# 4_Light_Screen.net
KiCad netlist of a schematic drawn in Altium Designer
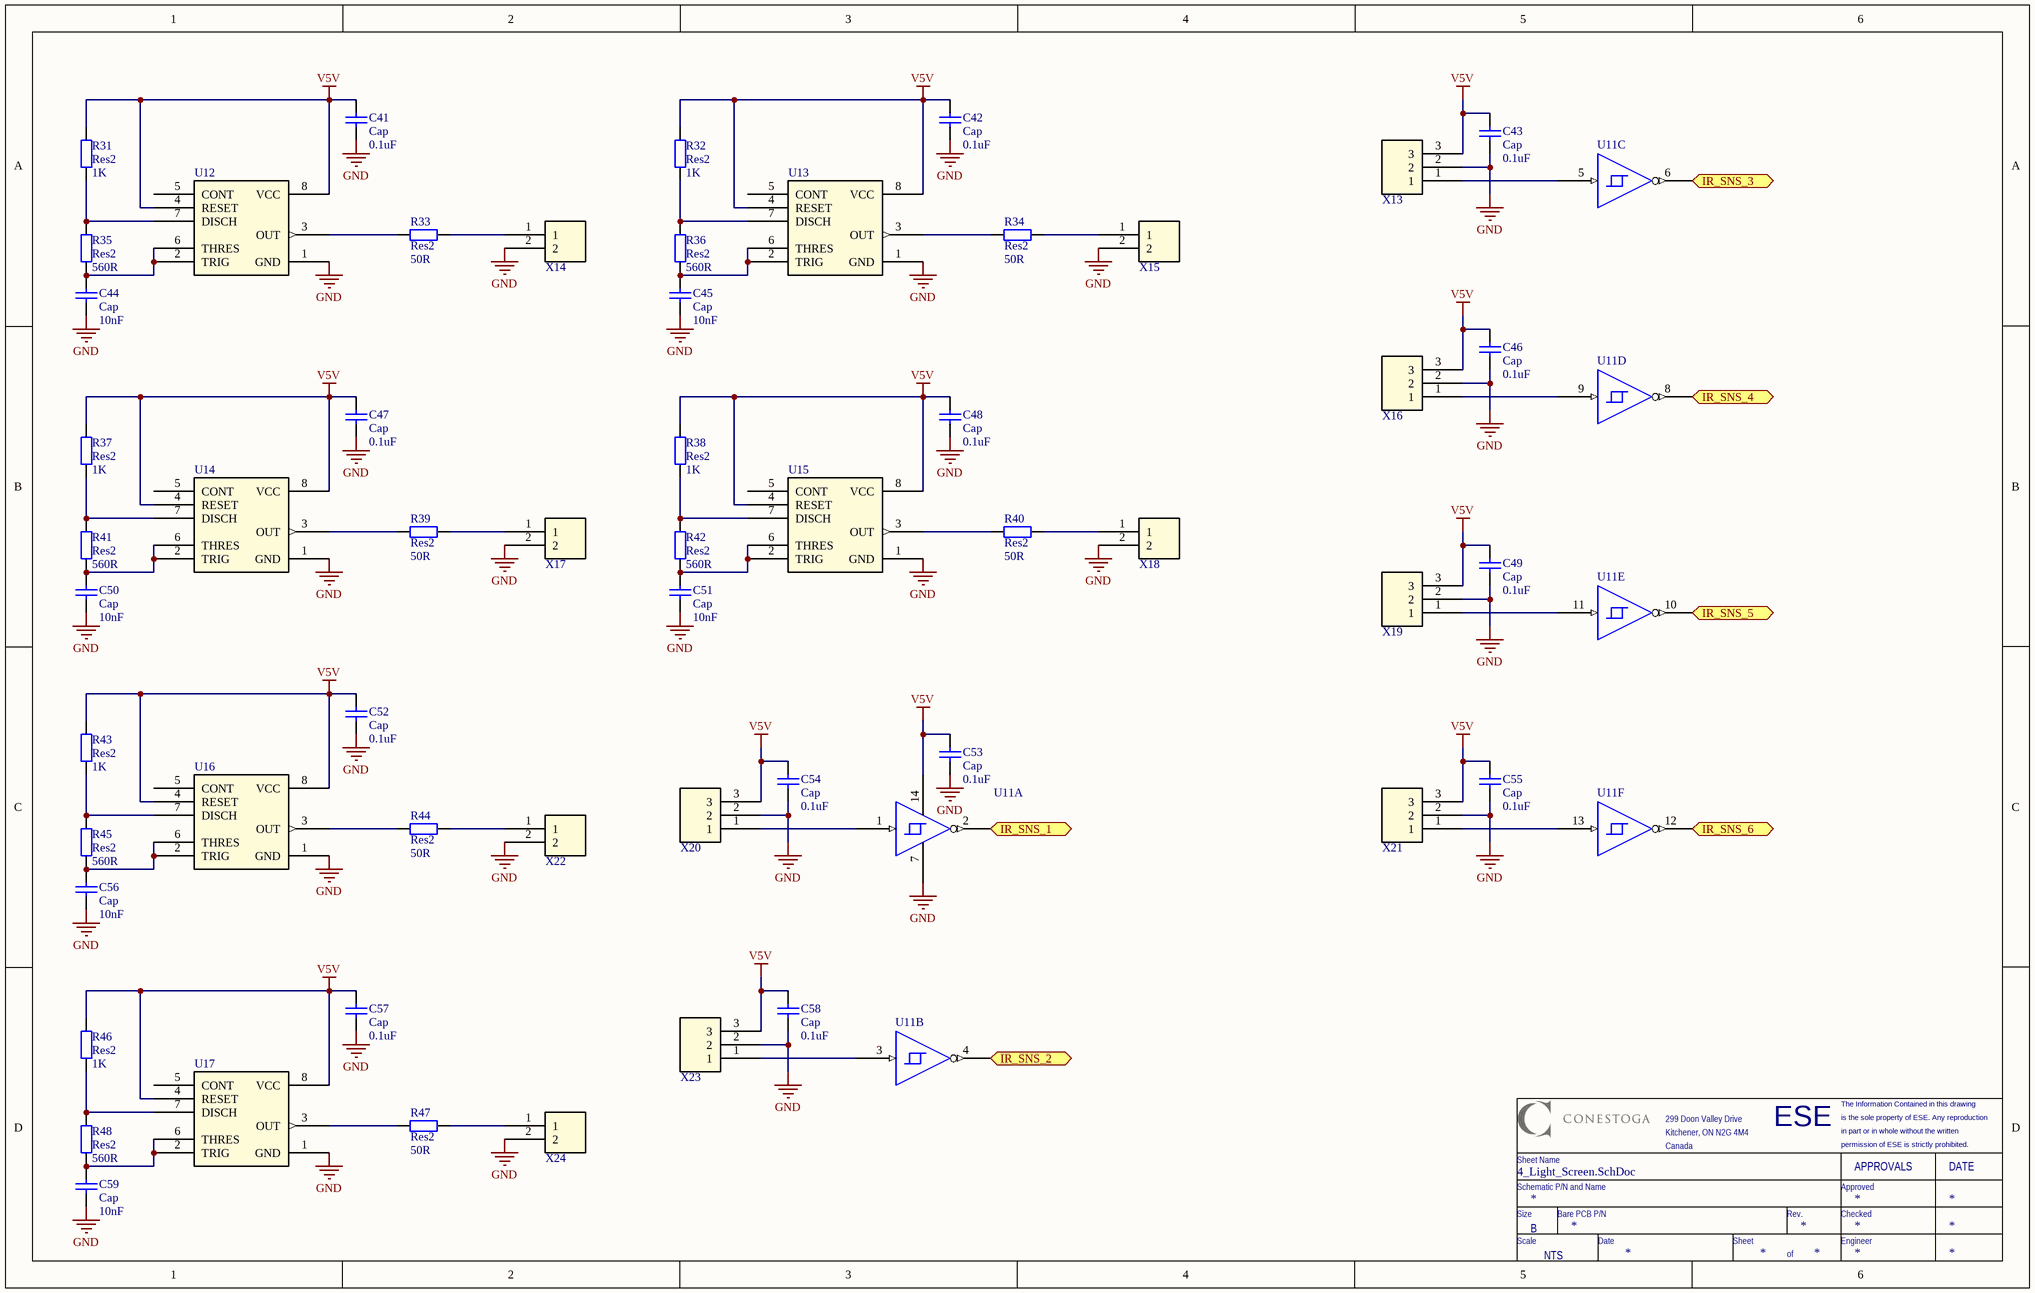
[diagram p0: 4_Light_Screen.SchDoc]

(export (version "E")
  (design (tool "Eeschema 10.0.6"))
  (components
    (comp (ref "C41")
      (value "Cap")
      (footprint "RAD-0.3")
      (description "Capacitor")
      (fields (field (name "ALTIUM_VALUE") "0.1uF") (field (name "PUBLISHER") "Altium Limited"))
      (libsource (lib "Miscellaneous Devices") (part "Cap"))
    )
    (comp (ref "C42")
      (value "Cap")
      (footprint "RAD-0.3")
      (description "Capacitor")
      (fields (field (name "ALTIUM_VALUE") "0.1uF") (field (name "PUBLISHER") "Altium Limited"))
      (libsource (lib "Miscellaneous Devices") (part "Cap"))
    )
    (comp (ref "C43")
      (value "Cap")
      (footprint "RAD-0.3")
      (description "Capacitor")
      (fields (field (name "ALTIUM_VALUE") "0.1uF") (field (name "PUBLISHER") "Altium Limited"))
      (libsource (lib "Miscellaneous Devices") (part "Cap"))
    )
    (comp (ref "C44")
      (value "Cap")
      (footprint "RAD-0.3")
      (description "Capacitor")
      (fields (field (name "ALTIUM_VALUE") "10nF") (field (name "PUBLISHER") "Altium Limited"))
      (libsource (lib "Miscellaneous Devices") (part "Cap"))
    )
    (comp (ref "C45")
      (value "Cap")
      (footprint "RAD-0.3")
      (description "Capacitor")
      (fields (field (name "ALTIUM_VALUE") "10nF") (field (name "PUBLISHER") "Altium Limited"))
      (libsource (lib "Miscellaneous Devices") (part "Cap"))
    )
    (comp (ref "C46")
      (value "Cap")
      (footprint "RAD-0.3")
      (description "Capacitor")
      (fields (field (name "ALTIUM_VALUE") "0.1uF") (field (name "PUBLISHER") "Altium Limited"))
      (libsource (lib "Miscellaneous Devices") (part "Cap"))
    )
    (comp (ref "C47")
      (value "Cap")
      (footprint "RAD-0.3")
      (description "Capacitor")
      (fields (field (name "ALTIUM_VALUE") "0.1uF") (field (name "PUBLISHER") "Altium Limited"))
      (libsource (lib "Miscellaneous Devices") (part "Cap"))
    )
    (comp (ref "C48")
      (value "Cap")
      (footprint "RAD-0.3")
      (description "Capacitor")
      (fields (field (name "ALTIUM_VALUE") "0.1uF") (field (name "PUBLISHER") "Altium Limited"))
      (libsource (lib "Miscellaneous Devices") (part "Cap"))
    )
    (comp (ref "C49")
      (value "Cap")
      (footprint "RAD-0.3")
      (description "Capacitor")
      (fields (field (name "ALTIUM_VALUE") "0.1uF") (field (name "PUBLISHER") "Altium Limited"))
      (libsource (lib "Miscellaneous Devices") (part "Cap"))
    )
    (comp (ref "C50")
      (value "Cap")
      (footprint "RAD-0.3")
      (description "Capacitor")
      (fields (field (name "ALTIUM_VALUE") "10nF") (field (name "PUBLISHER") "Altium Limited"))
      (libsource (lib "Miscellaneous Devices") (part "Cap"))
    )
    (comp (ref "C51")
      (value "Cap")
      (footprint "RAD-0.3")
      (description "Capacitor")
      (fields (field (name "ALTIUM_VALUE") "10nF") (field (name "PUBLISHER") "Altium Limited"))
      (libsource (lib "Miscellaneous Devices") (part "Cap"))
    )
    (comp (ref "C52")
      (value "Cap")
      (footprint "RAD-0.3")
      (description "Capacitor")
      (fields (field (name "ALTIUM_VALUE") "0.1uF") (field (name "PUBLISHER") "Altium Limited"))
      (libsource (lib "Miscellaneous Devices") (part "Cap"))
    )
    (comp (ref "C53")
      (value "Cap")
      (footprint "RAD-0.3")
      (description "Capacitor")
      (fields (field (name "ALTIUM_VALUE") "0.1uF") (field (name "PUBLISHER") "Altium Limited"))
      (libsource (lib "Miscellaneous Devices") (part "Cap"))
    )
    (comp (ref "C54")
      (value "Cap")
      (footprint "RAD-0.3")
      (description "Capacitor")
      (fields (field (name "ALTIUM_VALUE") "0.1uF") (field (name "PUBLISHER") "Altium Limited"))
      (libsource (lib "Miscellaneous Devices") (part "Cap"))
    )
    (comp (ref "C55")
      (value "Cap")
      (footprint "RAD-0.3")
      (description "Capacitor")
      (fields (field (name "ALTIUM_VALUE") "0.1uF") (field (name "PUBLISHER") "Altium Limited"))
      (libsource (lib "Miscellaneous Devices") (part "Cap"))
    )
    (comp (ref "C56")
      (value "Cap")
      (footprint "RAD-0.3")
      (description "Capacitor")
      (fields (field (name "ALTIUM_VALUE") "10nF") (field (name "PUBLISHER") "Altium Limited"))
      (libsource (lib "Miscellaneous Devices") (part "Cap"))
    )
    (comp (ref "C57")
      (value "Cap")
      (footprint "RAD-0.3")
      (description "Capacitor")
      (fields (field (name "ALTIUM_VALUE") "0.1uF") (field (name "PUBLISHER") "Altium Limited"))
      (libsource (lib "Miscellaneous Devices") (part "Cap"))
    )
    (comp (ref "C58")
      (value "Cap")
      (footprint "RAD-0.3")
      (description "Capacitor")
      (fields (field (name "ALTIUM_VALUE") "0.1uF") (field (name "PUBLISHER") "Altium Limited"))
      (libsource (lib "Miscellaneous Devices") (part "Cap"))
    )
    (comp (ref "C59")
      (value "Cap")
      (footprint "RAD-0.3")
      (description "Capacitor")
      (fields (field (name "ALTIUM_VALUE") "10nF") (field (name "PUBLISHER") "Altium Limited"))
      (libsource (lib "Miscellaneous Devices") (part "Cap"))
    )
    (comp (ref "R31")
      (value "Res2")
      (footprint "AXIAL-0.4")
      (description "Resistor")
      (fields (field (name "ALTIUM_VALUE") "1K") (field (name "PUBLISHER") "Altium Limited"))
      (libsource (lib "Miscellaneous Devices") (part "Res2"))
    )
    (comp (ref "R32")
      (value "Res2")
      (footprint "AXIAL-0.4")
      (description "Resistor")
      (fields (field (name "ALTIUM_VALUE") "1K") (field (name "PUBLISHER") "Altium Limited"))
      (libsource (lib "Miscellaneous Devices") (part "Res2"))
    )
    (comp (ref "R33")
      (value "Res2")
      (footprint "AXIAL-0.4")
      (description "Resistor")
      (fields (field (name "ALTIUM_VALUE") "50R") (field (name "PUBLISHER") "Altium Limited"))
      (libsource (lib "") (part "Res2_1"))
    )
    (comp (ref "R34")
      (value "Res2")
      (footprint "AXIAL-0.4")
      (description "Resistor")
      (fields (field (name "ALTIUM_VALUE") "50R") (field (name "PUBLISHER") "Altium Limited"))
      (libsource (lib "") (part "Res2_1"))
    )
    (comp (ref "R35")
      (value "Res2")
      (footprint "AXIAL-0.4")
      (description "Resistor")
      (fields (field (name "ALTIUM_VALUE") "560R") (field (name "PUBLISHER") "Altium Limited"))
      (libsource (lib "Miscellaneous Devices") (part "Res2"))
    )
    (comp (ref "R36")
      (value "Res2")
      (footprint "AXIAL-0.4")
      (description "Resistor")
      (fields (field (name "ALTIUM_VALUE") "560R") (field (name "PUBLISHER") "Altium Limited"))
      (libsource (lib "Miscellaneous Devices") (part "Res2"))
    )
    (comp (ref "R37")
      (value "Res2")
      (footprint "AXIAL-0.4")
      (description "Resistor")
      (fields (field (name "ALTIUM_VALUE") "1K") (field (name "PUBLISHER") "Altium Limited"))
      (libsource (lib "Miscellaneous Devices") (part "Res2"))
    )
    (comp (ref "R38")
      (value "Res2")
      (footprint "AXIAL-0.4")
      (description "Resistor")
      (fields (field (name "ALTIUM_VALUE") "1K") (field (name "PUBLISHER") "Altium Limited"))
      (libsource (lib "Miscellaneous Devices") (part "Res2"))
    )
    (comp (ref "R39")
      (value "Res2")
      (footprint "AXIAL-0.4")
      (description "Resistor")
      (fields (field (name "ALTIUM_VALUE") "50R") (field (name "PUBLISHER") "Altium Limited"))
      (libsource (lib "") (part "Res2_1"))
    )
    (comp (ref "R40")
      (value "Res2")
      (footprint "AXIAL-0.4")
      (description "Resistor")
      (fields (field (name "ALTIUM_VALUE") "50R") (field (name "PUBLISHER") "Altium Limited"))
      (libsource (lib "") (part "Res2_1"))
    )
    (comp (ref "R41")
      (value "Res2")
      (footprint "AXIAL-0.4")
      (description "Resistor")
      (fields (field (name "ALTIUM_VALUE") "560R") (field (name "PUBLISHER") "Altium Limited"))
      (libsource (lib "Miscellaneous Devices") (part "Res2"))
    )
    (comp (ref "R42")
      (value "Res2")
      (footprint "AXIAL-0.4")
      (description "Resistor")
      (fields (field (name "ALTIUM_VALUE") "560R") (field (name "PUBLISHER") "Altium Limited"))
      (libsource (lib "Miscellaneous Devices") (part "Res2"))
    )
    (comp (ref "R43")
      (value "Res2")
      (footprint "AXIAL-0.4")
      (description "Resistor")
      (fields (field (name "ALTIUM_VALUE") "1K") (field (name "PUBLISHER") "Altium Limited"))
      (libsource (lib "Miscellaneous Devices") (part "Res2"))
    )
    (comp (ref "R44")
      (value "Res2")
      (footprint "AXIAL-0.4")
      (description "Resistor")
      (fields (field (name "ALTIUM_VALUE") "50R") (field (name "PUBLISHER") "Altium Limited"))
      (libsource (lib "") (part "Res2_1"))
    )
    (comp (ref "R45")
      (value "Res2")
      (footprint "AXIAL-0.4")
      (description "Resistor")
      (fields (field (name "ALTIUM_VALUE") "560R") (field (name "PUBLISHER") "Altium Limited"))
      (libsource (lib "Miscellaneous Devices") (part "Res2"))
    )
    (comp (ref "R46")
      (value "Res2")
      (footprint "AXIAL-0.4")
      (description "Resistor")
      (fields (field (name "ALTIUM_VALUE") "1K") (field (name "PUBLISHER") "Altium Limited"))
      (libsource (lib "Miscellaneous Devices") (part "Res2"))
    )
    (comp (ref "R47")
      (value "Res2")
      (footprint "AXIAL-0.4")
      (description "Resistor")
      (fields (field (name "ALTIUM_VALUE") "50R") (field (name "PUBLISHER") "Altium Limited"))
      (libsource (lib "") (part "Res2_1"))
    )
    (comp (ref "R48")
      (value "Res2")
      (footprint "AXIAL-0.4")
      (description "Resistor")
      (fields (field (name "ALTIUM_VALUE") "560R") (field (name "PUBLISHER") "Altium Limited"))
      (libsource (lib "Miscellaneous Devices") (part "Res2"))
    )
    (comp (ref "U11")
      (value "IC HEX SCHMITT-TRIG INV 14-DIP")
      (footprint "14-DIP")
      (fields
        (field (name "DIGI-KEY_PART_NUMBER") "296-4368-5-ND")
        (field (name "MANUFACTUER_PART_NUMBER") "SN74ACT14N")
        (field (name "MANUFACTURER") "Texas Instruments")
      )
      (libsource (lib "thomas_lib") (part "IC HEX SCHMITT-TRIG INV 14-DIP"))
    )
    (comp (ref "U12")
      (value "IC OSC SINGLE TIMER 100KHZ 8-DIP")
      (footprint "thomas_lib:8-DIP")
      (fields
        (field (name "MANUFACTURER_PART_NUMBER") "NE555P")
        (field (name "DIGI-KEY_PART_NUMBER") "296-1411-5-ND")
        (field (name "MANUFACTURER") "Texas Instruments")
      )
      (libsource (lib "thomas_lib") (part "IC OSC SINGLE TIMER 100KHZ 8-DIP"))
    )
    (comp (ref "U13")
      (value "IC OSC SINGLE TIMER 100KHZ 8-DIP")
      (footprint "thomas_lib:8-DIP")
      (fields
        (field (name "MANUFACTURER_PART_NUMBER") "NE555P")
        (field (name "DIGI-KEY_PART_NUMBER") "296-1411-5-ND")
        (field (name "MANUFACTURER") "Texas Instruments")
      )
      (libsource (lib "thomas_lib") (part "IC OSC SINGLE TIMER 100KHZ 8-DIP"))
    )
    (comp (ref "U14")
      (value "IC OSC SINGLE TIMER 100KHZ 8-DIP")
      (footprint "thomas_lib:8-DIP")
      (fields
        (field (name "MANUFACTURER_PART_NUMBER") "NE555P")
        (field (name "DIGI-KEY_PART_NUMBER") "296-1411-5-ND")
        (field (name "MANUFACTURER") "Texas Instruments")
      )
      (libsource (lib "thomas_lib") (part "IC OSC SINGLE TIMER 100KHZ 8-DIP"))
    )
    (comp (ref "U15")
      (value "IC OSC SINGLE TIMER 100KHZ 8-DIP")
      (footprint "thomas_lib:8-DIP")
      (fields
        (field (name "MANUFACTURER_PART_NUMBER") "NE555P")
        (field (name "DIGI-KEY_PART_NUMBER") "296-1411-5-ND")
        (field (name "MANUFACTURER") "Texas Instruments")
      )
      (libsource (lib "thomas_lib") (part "IC OSC SINGLE TIMER 100KHZ 8-DIP"))
    )
    (comp (ref "U16")
      (value "IC OSC SINGLE TIMER 100KHZ 8-DIP")
      (footprint "thomas_lib:8-DIP")
      (fields
        (field (name "MANUFACTURER_PART_NUMBER") "NE555P")
        (field (name "DIGI-KEY_PART_NUMBER") "296-1411-5-ND")
        (field (name "MANUFACTURER") "Texas Instruments")
      )
      (libsource (lib "thomas_lib") (part "IC OSC SINGLE TIMER 100KHZ 8-DIP"))
    )
    (comp (ref "U17")
      (value "IC OSC SINGLE TIMER 100KHZ 8-DIP")
      (footprint "thomas_lib:8-DIP")
      (fields
        (field (name "MANUFACTURER_PART_NUMBER") "NE555P")
        (field (name "DIGI-KEY_PART_NUMBER") "296-1411-5-ND")
        (field (name "MANUFACTURER") "Texas Instruments")
      )
      (libsource (lib "thomas_lib") (part "IC OSC SINGLE TIMER 100KHZ 8-DIP"))
    )
    (comp (ref "X13")
      (value "TERM BLOCK HDR 3POS VERT 3.5MM")
      (footprint "WR-TBL-3211 3")
      (fields
        (field (name "DIGIKEY_PART_NUMBER") "732-2764-ND")
        (field (name "MANUFACTURER_PART_NUMBER") "691321100003")
        (field (name "MANUFACTURER") "Wurth Electronics Inc")
      )
      (libsource (lib "thomas_lib") (part "TERM BLOCK HDR 3POS VERT 3.5MM"))
    )
    (comp (ref "X14")
      (value "TERM BLOCK HDR 2POS VERT 3.5MM")
      (footprint "WR-TBL-3211 2")
      (fields
        (field (name "DIGIKEY_PART_NUMBER") "732-2763-ND")
        (field (name "MANUFACTURER_PART_NUMBER") "691321100002")
        (field (name "MANUFACTURER") "Wurth Electronics Inc")
      )
      (libsource (lib "thomas_lib") (part "TERM BLOCK HDR 2POS VERT 3.5MM"))
    )
    (comp (ref "X15")
      (value "TERM BLOCK HDR 2POS VERT 3.5MM")
      (footprint "WR-TBL-3211 2")
      (fields
        (field (name "DIGIKEY_PART_NUMBER") "732-2763-ND")
        (field (name "MANUFACTURER_PART_NUMBER") "691321100002")
        (field (name "MANUFACTURER") "Wurth Electronics Inc")
      )
      (libsource (lib "thomas_lib") (part "TERM BLOCK HDR 2POS VERT 3.5MM"))
    )
    (comp (ref "X16")
      (value "TERM BLOCK HDR 3POS VERT 3.5MM")
      (footprint "WR-TBL-3211 3")
      (fields
        (field (name "DIGIKEY_PART_NUMBER") "732-2764-ND")
        (field (name "MANUFACTURER_PART_NUMBER") "691321100003")
        (field (name "MANUFACTURER") "Wurth Electronics Inc")
      )
      (libsource (lib "thomas_lib") (part "TERM BLOCK HDR 3POS VERT 3.5MM"))
    )
    (comp (ref "X17")
      (value "TERM BLOCK HDR 2POS VERT 3.5MM")
      (footprint "WR-TBL-3211 2")
      (fields
        (field (name "DIGIKEY_PART_NUMBER") "732-2763-ND")
        (field (name "MANUFACTURER_PART_NUMBER") "691321100002")
        (field (name "MANUFACTURER") "Wurth Electronics Inc")
      )
      (libsource (lib "thomas_lib") (part "TERM BLOCK HDR 2POS VERT 3.5MM"))
    )
    (comp (ref "X18")
      (value "TERM BLOCK HDR 2POS VERT 3.5MM")
      (footprint "WR-TBL-3211 2")
      (fields
        (field (name "DIGIKEY_PART_NUMBER") "732-2763-ND")
        (field (name "MANUFACTURER_PART_NUMBER") "691321100002")
        (field (name "MANUFACTURER") "Wurth Electronics Inc")
      )
      (libsource (lib "thomas_lib") (part "TERM BLOCK HDR 2POS VERT 3.5MM"))
    )
    (comp (ref "X19")
      (value "TERM BLOCK HDR 3POS VERT 3.5MM")
      (footprint "WR-TBL-3211 3")
      (fields
        (field (name "DIGIKEY_PART_NUMBER") "732-2764-ND")
        (field (name "MANUFACTURER_PART_NUMBER") "691321100003")
        (field (name "MANUFACTURER") "Wurth Electronics Inc")
      )
      (libsource (lib "thomas_lib") (part "TERM BLOCK HDR 3POS VERT 3.5MM"))
    )
    (comp (ref "X20")
      (value "TERM BLOCK HDR 3POS VERT 3.5MM")
      (footprint "WR-TBL-3211 3")
      (fields
        (field (name "DIGIKEY_PART_NUMBER") "732-2764-ND")
        (field (name "MANUFACTURER_PART_NUMBER") "691321100003")
        (field (name "MANUFACTURER") "Wurth Electronics Inc")
      )
      (libsource (lib "thomas_lib") (part "TERM BLOCK HDR 3POS VERT 3.5MM"))
    )
    (comp (ref "X21")
      (value "TERM BLOCK HDR 3POS VERT 3.5MM")
      (footprint "WR-TBL-3211 3")
      (fields
        (field (name "DIGIKEY_PART_NUMBER") "732-2764-ND")
        (field (name "MANUFACTURER_PART_NUMBER") "691321100003")
        (field (name "MANUFACTURER") "Wurth Electronics Inc")
      )
      (libsource (lib "thomas_lib") (part "TERM BLOCK HDR 3POS VERT 3.5MM"))
    )
    (comp (ref "X22")
      (value "TERM BLOCK HDR 2POS VERT 3.5MM")
      (footprint "WR-TBL-3211 2")
      (fields
        (field (name "DIGIKEY_PART_NUMBER") "732-2763-ND")
        (field (name "MANUFACTURER_PART_NUMBER") "691321100002")
        (field (name "MANUFACTURER") "Wurth Electronics Inc")
      )
      (libsource (lib "thomas_lib") (part "TERM BLOCK HDR 2POS VERT 3.5MM"))
    )
    (comp (ref "X23")
      (value "TERM BLOCK HDR 3POS VERT 3.5MM")
      (footprint "WR-TBL-3211 3")
      (fields
        (field (name "DIGIKEY_PART_NUMBER") "732-2764-ND")
        (field (name "MANUFACTURER_PART_NUMBER") "691321100003")
        (field (name "MANUFACTURER") "Wurth Electronics Inc")
      )
      (libsource (lib "thomas_lib") (part "TERM BLOCK HDR 3POS VERT 3.5MM"))
    )
    (comp (ref "X24")
      (value "TERM BLOCK HDR 2POS VERT 3.5MM")
      (footprint "WR-TBL-3211 2")
      (fields
        (field (name "DIGIKEY_PART_NUMBER") "732-2763-ND")
        (field (name "MANUFACTURER_PART_NUMBER") "691321100002")
        (field (name "MANUFACTURER") "Wurth Electronics Inc")
      )
      (libsource (lib "thomas_lib") (part "TERM BLOCK HDR 2POS VERT 3.5MM"))
    )
  )
  (nets
    (net (code "1") (name "/IR_SNS_1") (class "Default")
      (node (ref "U11") (pin "2") (pinfunction "Y_2") (pintype "output"))
    )
    (net (code "2") (name "/IR_SNS_2") (class "Default")
      (node (ref "U11") (pin "4") (pinfunction "Y_4") (pintype "output"))
    )
    (net (code "3") (name "/IR_SNS_3") (class "Default")
      (node (ref "U11") (pin "6") (pinfunction "Y_6") (pintype "output"))
    )
    (net (code "4") (name "/IR_SNS_4") (class "Default")
      (node (ref "U11") (pin "8") (pinfunction "Y_8") (pintype "output"))
    )
    (net (code "5") (name "/IR_SNS_5") (class "Default")
      (node (ref "U11") (pin "10") (pinfunction "Y_10") (pintype "output"))
    )
    (net (code "6") (name "/IR_SNS_6") (class "Default")
      (node (ref "U11") (pin "12") (pinfunction "Y_12") (pintype "output"))
    )
    (net (code "7") (name "GND") (class "Default")
      (node (ref "C41") (pin "1") (pinfunction "1_1") (pintype "passive"))
      (node (ref "C42") (pin "1") (pinfunction "1_1") (pintype "passive"))
      (node (ref "C43") (pin "1") (pinfunction "1_1") (pintype "passive"))
      (node (ref "C44") (pin "1") (pinfunction "1_1") (pintype "passive"))
      (node (ref "C45") (pin "1") (pinfunction "1_1") (pintype "passive"))
      (node (ref "C46") (pin "1") (pinfunction "1_1") (pintype "passive"))
      (node (ref "C47") (pin "1") (pinfunction "1_1") (pintype "passive"))
      (node (ref "C48") (pin "1") (pinfunction "1_1") (pintype "passive"))
      (node (ref "C49") (pin "1") (pinfunction "1_1") (pintype "passive"))
      (node (ref "C50") (pin "1") (pinfunction "1_1") (pintype "passive"))
      (node (ref "C51") (pin "1") (pinfunction "1_1") (pintype "passive"))
      (node (ref "C52") (pin "1") (pinfunction "1_1") (pintype "passive"))
      (node (ref "C53") (pin "1") (pinfunction "1_1") (pintype "passive"))
      (node (ref "C54") (pin "1") (pinfunction "1_1") (pintype "passive"))
      (node (ref "C55") (pin "1") (pinfunction "1_1") (pintype "passive"))
      (node (ref "C56") (pin "1") (pinfunction "1_1") (pintype "passive"))
      (node (ref "C57") (pin "1") (pinfunction "1_1") (pintype "passive"))
      (node (ref "C58") (pin "1") (pinfunction "1_1") (pintype "passive"))
      (node (ref "C59") (pin "1") (pinfunction "1_1") (pintype "passive"))
      (node (ref "U11") (pin "7") (pinfunction "GND_POWER_7") (pintype "power_in"))
      (node (ref "U12") (pin "1") (pinfunction "GND_1") (pintype "power_in"))
      (node (ref "U13") (pin "1") (pinfunction "GND_1") (pintype "power_in"))
      (node (ref "U14") (pin "1") (pinfunction "GND_1") (pintype "power_in"))
      (node (ref "U15") (pin "1") (pinfunction "GND_1") (pintype "power_in"))
      (node (ref "U16") (pin "1") (pinfunction "GND_1") (pintype "power_in"))
      (node (ref "U17") (pin "1") (pinfunction "GND_1") (pintype "power_in"))
      (node (ref "X13") (pin "2") (pinfunction "2_2") (pintype "passive"))
      (node (ref "X14") (pin "2") (pinfunction "2_2") (pintype "passive"))
      (node (ref "X15") (pin "2") (pinfunction "2_2") (pintype "passive"))
      (node (ref "X16") (pin "2") (pinfunction "2_2") (pintype "passive"))
      (node (ref "X17") (pin "2") (pinfunction "2_2") (pintype "passive"))
      (node (ref "X18") (pin "2") (pinfunction "2_2") (pintype "passive"))
      (node (ref "X19") (pin "2") (pinfunction "2_2") (pintype "passive"))
      (node (ref "X20") (pin "2") (pinfunction "2_2") (pintype "passive"))
      (node (ref "X21") (pin "2") (pinfunction "2_2") (pintype "passive"))
      (node (ref "X22") (pin "2") (pinfunction "2_2") (pintype "passive"))
      (node (ref "X23") (pin "2") (pinfunction "2_2") (pintype "passive"))
      (node (ref "X24") (pin "2") (pinfunction "2_2") (pintype "passive"))
    )
    (net (code "8") (name "Net-(R33-Pad1)") (class "Default")
      (node (ref "R33") (pin "1") (pinfunction "1_1") (pintype "passive"))
      (node (ref "X14") (pin "1") (pinfunction "1_1") (pintype "passive"))
    )
    (net (code "9") (name "Net-(R34-Pad1)") (class "Default")
      (node (ref "R34") (pin "1") (pinfunction "1_1") (pintype "passive"))
      (node (ref "X15") (pin "1") (pinfunction "1_1") (pintype "passive"))
    )
    (net (code "10") (name "Net-(R39-Pad1)") (class "Default")
      (node (ref "R39") (pin "1") (pinfunction "1_1") (pintype "passive"))
      (node (ref "X17") (pin "1") (pinfunction "1_1") (pintype "passive"))
    )
    (net (code "11") (name "Net-(R40-Pad1)") (class "Default")
      (node (ref "R40") (pin "1") (pinfunction "1_1") (pintype "passive"))
      (node (ref "X18") (pin "1") (pinfunction "1_1") (pintype "passive"))
    )
    (net (code "12") (name "Net-(R44-Pad1)") (class "Default")
      (node (ref "R44") (pin "1") (pinfunction "1_1") (pintype "passive"))
      (node (ref "X22") (pin "1") (pinfunction "1_1") (pintype "passive"))
    )
    (net (code "13") (name "Net-(R47-Pad1)") (class "Default")
      (node (ref "R47") (pin "1") (pinfunction "1_1") (pintype "passive"))
      (node (ref "X24") (pin "1") (pinfunction "1_1") (pintype "passive"))
    )
    (net (code "14") (name "Net-(U11A-A)") (class "Default")
      (node (ref "U11") (pin "1") (pinfunction "A_1") (pintype "input"))
      (node (ref "X20") (pin "1") (pinfunction "1_1") (pintype "passive"))
    )
    (net (code "15") (name "Net-(U11B-A)") (class "Default")
      (node (ref "U11") (pin "3") (pinfunction "A_3") (pintype "input"))
      (node (ref "X23") (pin "1") (pinfunction "1_1") (pintype "passive"))
    )
    (net (code "16") (name "Net-(U11C-A)") (class "Default")
      (node (ref "U11") (pin "5") (pinfunction "A_5") (pintype "input"))
      (node (ref "X13") (pin "1") (pinfunction "1_1") (pintype "passive"))
    )
    (net (code "17") (name "Net-(U11D-A)") (class "Default")
      (node (ref "U11") (pin "9") (pinfunction "A_9") (pintype "input"))
      (node (ref "X16") (pin "1") (pinfunction "1_1") (pintype "passive"))
    )
    (net (code "18") (name "Net-(U11E-A)") (class "Default")
      (node (ref "U11") (pin "11") (pinfunction "A_11") (pintype "input"))
      (node (ref "X19") (pin "1") (pinfunction "1_1") (pintype "passive"))
    )
    (net (code "19") (name "Net-(U11F-A)") (class "Default")
      (node (ref "U11") (pin "13") (pinfunction "A_13") (pintype "input"))
      (node (ref "X21") (pin "1") (pinfunction "1_1") (pintype "passive"))
    )
    (net (code "20") (name "Net-(U12-DISCH)") (class "Default")
      (node (ref "R31") (pin "2") (pinfunction "2_2") (pintype "passive"))
      (node (ref "R35") (pin "1") (pinfunction "1_1") (pintype "passive"))
      (node (ref "U12") (pin "7") (pinfunction "DISCH_7") (pintype "passive"))
    )
    (net (code "21") (name "Net-(U12-OUT)") (class "Default")
      (node (ref "R33") (pin "2") (pinfunction "2_2") (pintype "passive"))
      (node (ref "U12") (pin "3") (pinfunction "OUT_3") (pintype "output"))
    )
    (net (code "22") (name "Net-(U12-THRES)") (class "Default")
      (node (ref "C44") (pin "2") (pinfunction "2_2") (pintype "passive"))
      (node (ref "R35") (pin "2") (pinfunction "2_2") (pintype "passive"))
      (node (ref "U12") (pin "2") (pinfunction "TRIG_2") (pintype "passive"))
      (node (ref "U12") (pin "6") (pinfunction "THRES_6") (pintype "power_in"))
    )
    (net (code "23") (name "Net-(U13-DISCH)") (class "Default")
      (node (ref "R32") (pin "2") (pinfunction "2_2") (pintype "passive"))
      (node (ref "R36") (pin "1") (pinfunction "1_1") (pintype "passive"))
      (node (ref "U13") (pin "7") (pinfunction "DISCH_7") (pintype "passive"))
    )
    (net (code "24") (name "Net-(U13-OUT)") (class "Default")
      (node (ref "R34") (pin "2") (pinfunction "2_2") (pintype "passive"))
      (node (ref "U13") (pin "3") (pinfunction "OUT_3") (pintype "output"))
    )
    (net (code "25") (name "Net-(U13-THRES)") (class "Default")
      (node (ref "C45") (pin "2") (pinfunction "2_2") (pintype "passive"))
      (node (ref "R36") (pin "2") (pinfunction "2_2") (pintype "passive"))
      (node (ref "U13") (pin "2") (pinfunction "TRIG_2") (pintype "passive"))
      (node (ref "U13") (pin "6") (pinfunction "THRES_6") (pintype "power_in"))
    )
    (net (code "26") (name "Net-(U14-DISCH)") (class "Default")
      (node (ref "R37") (pin "2") (pinfunction "2_2") (pintype "passive"))
      (node (ref "R41") (pin "1") (pinfunction "1_1") (pintype "passive"))
      (node (ref "U14") (pin "7") (pinfunction "DISCH_7") (pintype "passive"))
    )
    (net (code "27") (name "Net-(U14-OUT)") (class "Default")
      (node (ref "R39") (pin "2") (pinfunction "2_2") (pintype "passive"))
      (node (ref "U14") (pin "3") (pinfunction "OUT_3") (pintype "output"))
    )
    (net (code "28") (name "Net-(U14-THRES)") (class "Default")
      (node (ref "C50") (pin "2") (pinfunction "2_2") (pintype "passive"))
      (node (ref "R41") (pin "2") (pinfunction "2_2") (pintype "passive"))
      (node (ref "U14") (pin "2") (pinfunction "TRIG_2") (pintype "passive"))
      (node (ref "U14") (pin "6") (pinfunction "THRES_6") (pintype "power_in"))
    )
    (net (code "29") (name "Net-(U15-DISCH)") (class "Default")
      (node (ref "R38") (pin "2") (pinfunction "2_2") (pintype "passive"))
      (node (ref "R42") (pin "1") (pinfunction "1_1") (pintype "passive"))
      (node (ref "U15") (pin "7") (pinfunction "DISCH_7") (pintype "passive"))
    )
    (net (code "30") (name "Net-(U15-OUT)") (class "Default")
      (node (ref "R40") (pin "2") (pinfunction "2_2") (pintype "passive"))
      (node (ref "U15") (pin "3") (pinfunction "OUT_3") (pintype "output"))
    )
    (net (code "31") (name "Net-(U15-THRES)") (class "Default")
      (node (ref "C51") (pin "2") (pinfunction "2_2") (pintype "passive"))
      (node (ref "R42") (pin "2") (pinfunction "2_2") (pintype "passive"))
      (node (ref "U15") (pin "2") (pinfunction "TRIG_2") (pintype "passive"))
      (node (ref "U15") (pin "6") (pinfunction "THRES_6") (pintype "power_in"))
    )
    (net (code "32") (name "Net-(U16-DISCH)") (class "Default")
      (node (ref "R43") (pin "2") (pinfunction "2_2") (pintype "passive"))
      (node (ref "R45") (pin "1") (pinfunction "1_1") (pintype "passive"))
      (node (ref "U16") (pin "7") (pinfunction "DISCH_7") (pintype "passive"))
    )
    (net (code "33") (name "Net-(U16-OUT)") (class "Default")
      (node (ref "R44") (pin "2") (pinfunction "2_2") (pintype "passive"))
      (node (ref "U16") (pin "3") (pinfunction "OUT_3") (pintype "output"))
    )
    (net (code "34") (name "Net-(U16-THRES)") (class "Default")
      (node (ref "C56") (pin "2") (pinfunction "2_2") (pintype "passive"))
      (node (ref "R45") (pin "2") (pinfunction "2_2") (pintype "passive"))
      (node (ref "U16") (pin "2") (pinfunction "TRIG_2") (pintype "passive"))
      (node (ref "U16") (pin "6") (pinfunction "THRES_6") (pintype "power_in"))
    )
    (net (code "35") (name "Net-(U17-DISCH)") (class "Default")
      (node (ref "R46") (pin "2") (pinfunction "2_2") (pintype "passive"))
      (node (ref "R48") (pin "1") (pinfunction "1_1") (pintype "passive"))
      (node (ref "U17") (pin "7") (pinfunction "DISCH_7") (pintype "passive"))
    )
    (net (code "36") (name "Net-(U17-OUT)") (class "Default")
      (node (ref "R47") (pin "2") (pinfunction "2_2") (pintype "passive"))
      (node (ref "U17") (pin "3") (pinfunction "OUT_3") (pintype "output"))
    )
    (net (code "37") (name "Net-(U17-THRES)") (class "Default")
      (node (ref "C59") (pin "2") (pinfunction "2_2") (pintype "passive"))
      (node (ref "R48") (pin "2") (pinfunction "2_2") (pintype "passive"))
      (node (ref "U17") (pin "2") (pinfunction "TRIG_2") (pintype "passive"))
      (node (ref "U17") (pin "6") (pinfunction "THRES_6") (pintype "power_in"))
    )
    (net (code "38") (name "V5V") (class "Default")
      (node (ref "C41") (pin "2") (pinfunction "2_2") (pintype "passive"))
      (node (ref "C42") (pin "2") (pinfunction "2_2") (pintype "passive"))
      (node (ref "C43") (pin "2") (pinfunction "2_2") (pintype "passive"))
      (node (ref "C46") (pin "2") (pinfunction "2_2") (pintype "passive"))
      (node (ref "C47") (pin "2") (pinfunction "2_2") (pintype "passive"))
      (node (ref "C48") (pin "2") (pinfunction "2_2") (pintype "passive"))
      (node (ref "C49") (pin "2") (pinfunction "2_2") (pintype "passive"))
      (node (ref "C52") (pin "2") (pinfunction "2_2") (pintype "passive"))
      (node (ref "C53") (pin "2") (pinfunction "2_2") (pintype "passive"))
      (node (ref "C54") (pin "2") (pinfunction "2_2") (pintype "passive"))
      (node (ref "C55") (pin "2") (pinfunction "2_2") (pintype "passive"))
      (node (ref "C57") (pin "2") (pinfunction "2_2") (pintype "passive"))
      (node (ref "C58") (pin "2") (pinfunction "2_2") (pintype "passive"))
      (node (ref "R31") (pin "1") (pinfunction "1_1") (pintype "passive"))
      (node (ref "R32") (pin "1") (pinfunction "1_1") (pintype "passive"))
      (node (ref "R37") (pin "1") (pinfunction "1_1") (pintype "passive"))
      (node (ref "R38") (pin "1") (pinfunction "1_1") (pintype "passive"))
      (node (ref "R43") (pin "1") (pinfunction "1_1") (pintype "passive"))
      (node (ref "R46") (pin "1") (pinfunction "1_1") (pintype "passive"))
      (node (ref "U11") (pin "14") (pinfunction "VCC_14") (pintype "power_in"))
      (node (ref "U12") (pin "4") (pinfunction "RESET_4") (pintype "power_in"))
      (node (ref "U12") (pin "8") (pinfunction "VCC_8") (pintype "power_in"))
      (node (ref "U13") (pin "4") (pinfunction "RESET_4") (pintype "power_in"))
      (node (ref "U13") (pin "8") (pinfunction "VCC_8") (pintype "power_in"))
      (node (ref "U14") (pin "4") (pinfunction "RESET_4") (pintype "power_in"))
      (node (ref "U14") (pin "8") (pinfunction "VCC_8") (pintype "power_in"))
      (node (ref "U15") (pin "4") (pinfunction "RESET_4") (pintype "power_in"))
      (node (ref "U15") (pin "8") (pinfunction "VCC_8") (pintype "power_in"))
      (node (ref "U16") (pin "4") (pinfunction "RESET_4") (pintype "power_in"))
      (node (ref "U16") (pin "8") (pinfunction "VCC_8") (pintype "power_in"))
      (node (ref "U17") (pin "4") (pinfunction "RESET_4") (pintype "power_in"))
      (node (ref "U17") (pin "8") (pinfunction "VCC_8") (pintype "power_in"))
      (node (ref "X13") (pin "3") (pinfunction "3_3") (pintype "passive"))
      (node (ref "X16") (pin "3") (pinfunction "3_3") (pintype "passive"))
      (node (ref "X19") (pin "3") (pinfunction "3_3") (pintype "passive"))
      (node (ref "X20") (pin "3") (pinfunction "3_3") (pintype "passive"))
      (node (ref "X21") (pin "3") (pinfunction "3_3") (pintype "passive"))
      (node (ref "X23") (pin "3") (pinfunction "3_3") (pintype "passive"))
    )
    (net (code "39") (name "unconnected-(U12-CONT-Pad5)") (class "Default")
      (node (ref "U12") (pin "5") (pinfunction "CONT_5") (pintype "passive"))
    )
    (net (code "40") (name "unconnected-(U13-CONT-Pad5)") (class "Default")
      (node (ref "U13") (pin "5") (pinfunction "CONT_5") (pintype "passive"))
    )
    (net (code "41") (name "unconnected-(U14-CONT-Pad5)") (class "Default")
      (node (ref "U14") (pin "5") (pinfunction "CONT_5") (pintype "passive"))
    )
    (net (code "42") (name "unconnected-(U15-CONT-Pad5)") (class "Default")
      (node (ref "U15") (pin "5") (pinfunction "CONT_5") (pintype "passive"))
    )
    (net (code "43") (name "unconnected-(U16-CONT-Pad5)") (class "Default")
      (node (ref "U16") (pin "5") (pinfunction "CONT_5") (pintype "passive"))
    )
    (net (code "44") (name "unconnected-(U17-CONT-Pad5)") (class "Default")
      (node (ref "U17") (pin "5") (pinfunction "CONT_5") (pintype "passive"))
    )
  )
)
